# MBC1_1-3.net
KiCad netlist of a schematic drawn in EAGLE
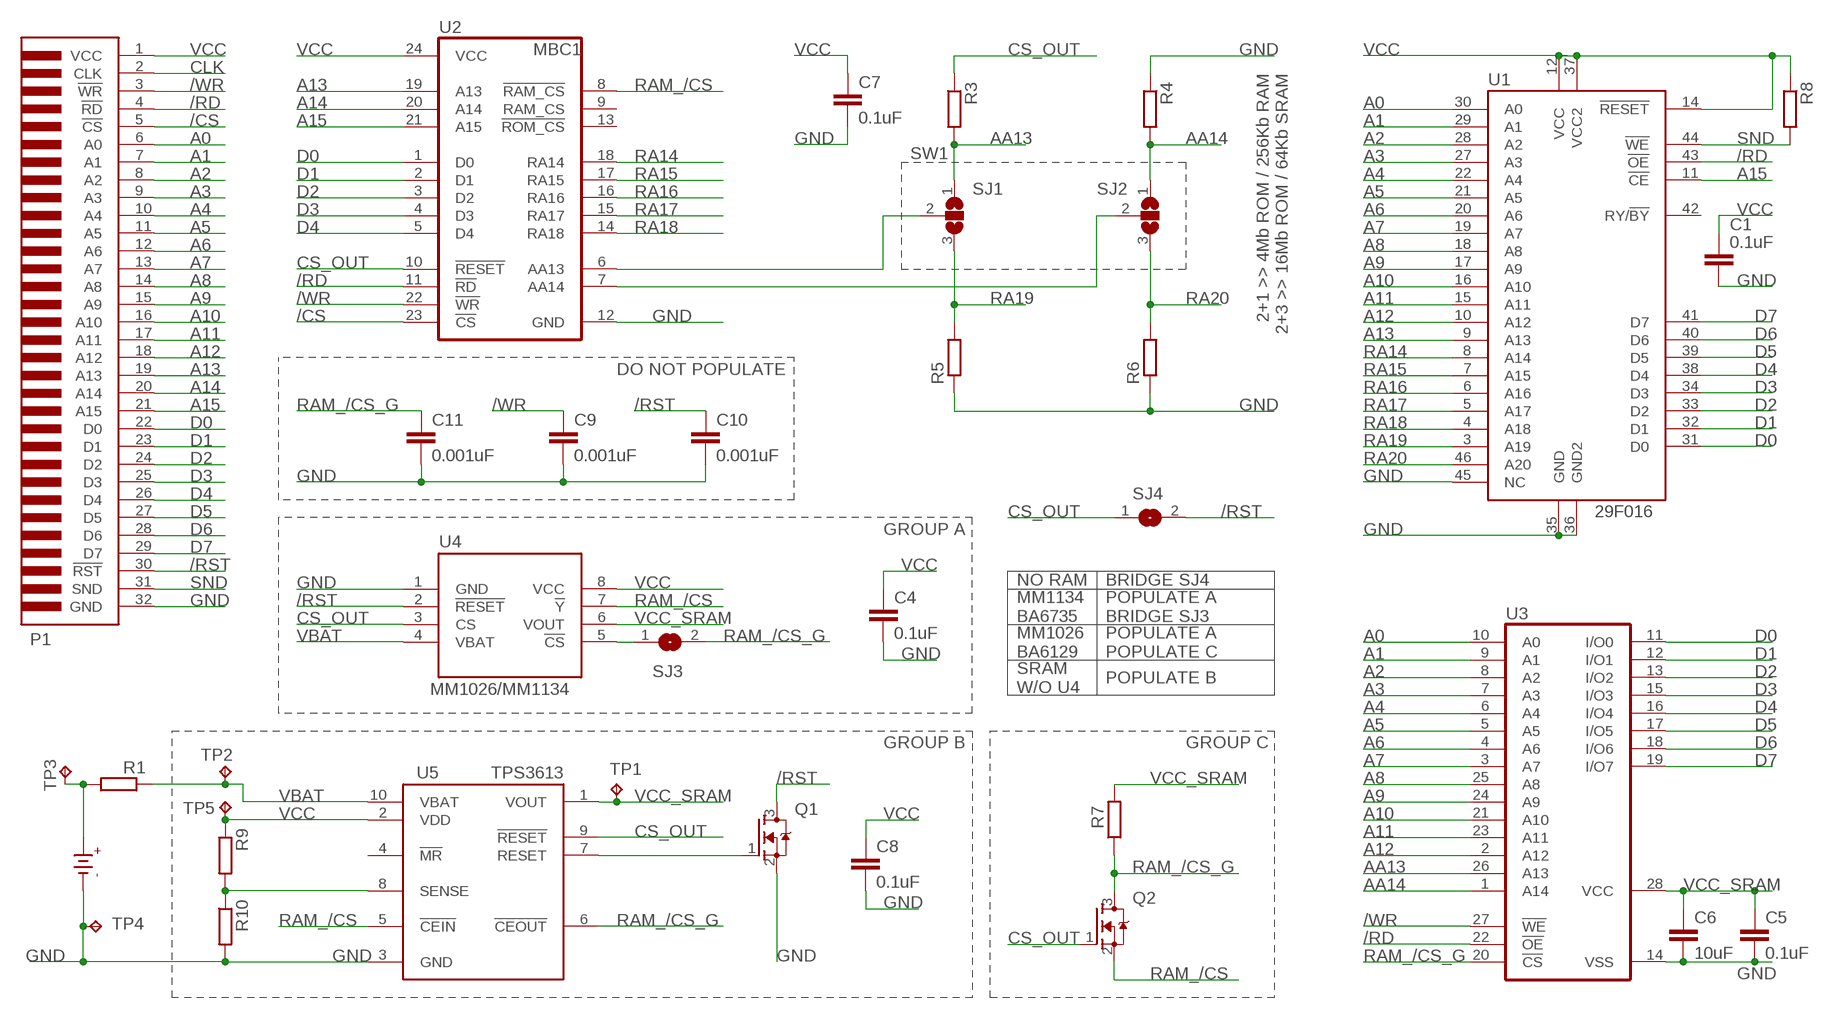
[diagram p0: schematic, sheet 1]

(export (version "E")
  (design (tool "Eeschema 10.0.6"))
  (components
    (comp (ref "B1")
      (value "CR2025")
      (footprint "eagle-import:CR2025")
      (libsource (lib "eagle-import") (part "CR2025"))
    )
    (comp (ref "C1")
      (value "0.1uF")
      (footprint "eagle-import:C0603")
      (libsource (lib "eagle-import") (part "C-EUC0603"))
    )
    (comp (ref "C4")
      (value "0.1uF")
      (footprint "eagle-import:C0603")
      (libsource (lib "eagle-import") (part "C-EUC0603"))
    )
    (comp (ref "C5")
      (value "0.1uF")
      (footprint "eagle-import:C0603")
      (libsource (lib "eagle-import") (part "C-EUC0603"))
    )
    (comp (ref "C6")
      (value "10uF")
      (footprint "eagle-import:C0603")
      (libsource (lib "eagle-import") (part "C-EUC0603"))
    )
    (comp (ref "C7")
      (value "0.1uF")
      (footprint "eagle-import:C0603")
      (libsource (lib "eagle-import") (part "C-EUC0603"))
    )
    (comp (ref "C8")
      (value "0.1uF")
      (footprint "eagle-import:C0603")
      (libsource (lib "eagle-import") (part "C-EUC0603"))
    )
    (comp (ref "C9")
      (value "0.001uF")
      (footprint "eagle-import:C0603")
      (libsource (lib "eagle-import") (part "C-EUC0603"))
    )
    (comp (ref "C10")
      (value "0.001uF")
      (footprint "eagle-import:C0603")
      (libsource (lib "eagle-import") (part "C-EUC0603"))
    )
    (comp (ref "C11")
      (value "0.001uF")
      (footprint "eagle-import:C0603")
      (libsource (lib "eagle-import") (part "C-EUC0603"))
    )
    (comp (ref "P1")
      (value "GBC_CART")
      (footprint "eagle-import:GBC_CART")
      (libsource (lib "eagle-import") (part "GBC_CART"))
    )
    (comp (ref "Q1")
      (value "2N7002")
      (footprint "eagle-import:SOT23")
      (libsource (lib "eagle-import") (part "MOSFET-NREFLOW"))
    )
    (comp (ref "Q2")
      (value "2N7002")
      (footprint "eagle-import:SOT23")
      (libsource (lib "eagle-import") (part "MOSFET-NREFLOW"))
    )
    (comp (ref "R1")
      (value "RR0603")
      (footprint "eagle-import:R0603")
      (libsource (lib "eagle-import") (part "RR0603"))
    )
    (comp (ref "R3")
      (value "RR0603")
      (footprint "eagle-import:R0603")
      (libsource (lib "eagle-import") (part "RR0603"))
    )
    (comp (ref "R4")
      (value "RR0603")
      (footprint "eagle-import:R0603")
      (libsource (lib "eagle-import") (part "RR0603"))
    )
    (comp (ref "R5")
      (value "RR0603")
      (footprint "eagle-import:R0603")
      (libsource (lib "eagle-import") (part "RR0603"))
    )
    (comp (ref "R6")
      (value "RR0603")
      (footprint "eagle-import:R0603")
      (libsource (lib "eagle-import") (part "RR0603"))
    )
    (comp (ref "R7")
      (value "RR0603")
      (footprint "eagle-import:R0603")
      (libsource (lib "eagle-import") (part "RR0603"))
    )
    (comp (ref "R8")
      (value "RR0603")
      (footprint "eagle-import:R0603")
      (libsource (lib "eagle-import") (part "RR0603"))
    )
    (comp (ref "R9")
      (value "RR0603")
      (footprint "eagle-import:R0603")
      (libsource (lib "eagle-import") (part "RR0603"))
    )
    (comp (ref "R10")
      (value "RR0603")
      (footprint "eagle-import:R0603")
      (libsource (lib "eagle-import") (part "RR0603"))
    )
    (comp (ref "SJ1")
      (value "SJ2W")
      (footprint "eagle-import:SJ_2")
      (libsource (lib "eagle-import") (part "SJ2W"))
    )
    (comp (ref "SJ2")
      (value "SJ2W")
      (footprint "eagle-import:SJ_2")
      (libsource (lib "eagle-import") (part "SJ2W"))
    )
    (comp (ref "SJ3") (value "SJ") (footprint "eagle-import:SJ") (libsource (lib "eagle-import") (part "SJ")))
    (comp (ref "SJ4") (value "SJ") (footprint "eagle-import:SJ") (libsource (lib "eagle-import") (part "SJ")))
    (comp (ref "TP1")
      (value "TPB1,27")
      (footprint "eagle-import:B1,27")
      (libsource (lib "eagle-import") (part "TPB1,27"))
    )
    (comp (ref "TP2")
      (value "TPB1,27")
      (footprint "eagle-import:B1,27")
      (libsource (lib "eagle-import") (part "TPB1,27"))
    )
    (comp (ref "TP3")
      (value "TPB1,27")
      (footprint "eagle-import:B1,27")
      (libsource (lib "eagle-import") (part "TPB1,27"))
    )
    (comp (ref "TP4")
      (value "TPB1,27")
      (footprint "eagle-import:B1,27")
      (libsource (lib "eagle-import") (part "TPB1,27"))
    )
    (comp (ref "TP5")
      (value "TPB1,27")
      (footprint "eagle-import:B1,27")
      (libsource (lib "eagle-import") (part "TPB1,27"))
    )
    (comp (ref "U1")
      (value "29F016")
      (footprint "eagle-import:TSOP-48")
      (libsource (lib "eagle-import") (part "29F016"))
    )
    (comp (ref "U2")
      (value "MBC1")
      (footprint "eagle-import:SOP-24")
      (libsource (lib "eagle-import") (part "MBC1"))
    )
    (comp (ref "U3")
      (value "62256_SRAM")
      (footprint "eagle-import:SOP-28L")
      (fields (field (name "MPN") "CY62256VNLL-70SNXI"))
      (libsource (lib "eagle-import") (part "62256_SRAM"))
    )
    (comp (ref "U4")
      (value "MM1134")
      (footprint "eagle-import:SOIC-8")
      (libsource (lib "eagle-import") (part "MM1134"))
    )
    (comp (ref "U5")
      (value "TPS3613")
      (footprint "eagle-import:MSOP-10")
      (libsource (lib "eagle-import") (part "TPS3613"))
    )
  )
  (nets
    (net (code "1") (name "/A0") (class "Default")
      (node (ref "P1") (pin "6") (pinfunction "A0_6") (pintype "output"))
      (node (ref "U1") (pin "30") (pinfunction "A0_30") (pintype "input"))
      (node (ref "U3") (pin "10") (pinfunction "A0_10") (pintype "input"))
    )
    (net (code "2") (name "/A1") (class "Default")
      (node (ref "P1") (pin "7") (pinfunction "A1_7") (pintype "output"))
      (node (ref "U1") (pin "29") (pinfunction "A1_29") (pintype "input"))
      (node (ref "U3") (pin "9") (pinfunction "A1_9") (pintype "input"))
    )
    (net (code "3") (name "/A2") (class "Default")
      (node (ref "P1") (pin "8") (pinfunction "A2_8") (pintype "output"))
      (node (ref "U1") (pin "28") (pinfunction "A2_28") (pintype "input"))
      (node (ref "U3") (pin "8") (pinfunction "A2_8") (pintype "input"))
    )
    (net (code "4") (name "/A3") (class "Default")
      (node (ref "P1") (pin "9") (pinfunction "A3_9") (pintype "output"))
      (node (ref "U1") (pin "27") (pinfunction "A3_27") (pintype "input"))
      (node (ref "U3") (pin "7") (pinfunction "A3_7") (pintype "input"))
    )
    (net (code "5") (name "/A4") (class "Default")
      (node (ref "P1") (pin "10") (pinfunction "A4_10") (pintype "output"))
      (node (ref "U1") (pin "22") (pinfunction "A4_22") (pintype "input"))
      (node (ref "U3") (pin "6") (pinfunction "A4_6") (pintype "input"))
    )
    (net (code "6") (name "/A5") (class "Default")
      (node (ref "P1") (pin "11") (pinfunction "A5_11") (pintype "output"))
      (node (ref "U1") (pin "21") (pinfunction "A5_21") (pintype "input"))
      (node (ref "U3") (pin "5") (pinfunction "A5_5") (pintype "input"))
    )
    (net (code "7") (name "/A6") (class "Default")
      (node (ref "P1") (pin "12") (pinfunction "A6_12") (pintype "output"))
      (node (ref "U1") (pin "20") (pinfunction "A6_20") (pintype "input"))
      (node (ref "U3") (pin "4") (pinfunction "A6_4") (pintype "input"))
    )
    (net (code "8") (name "/A7") (class "Default")
      (node (ref "P1") (pin "13") (pinfunction "A7_13") (pintype "output"))
      (node (ref "U1") (pin "19") (pinfunction "A7_19") (pintype "input"))
      (node (ref "U3") (pin "3") (pinfunction "A7_3") (pintype "input"))
    )
    (net (code "9") (name "/A8") (class "Default")
      (node (ref "P1") (pin "14") (pinfunction "A8_14") (pintype "output"))
      (node (ref "U1") (pin "18") (pinfunction "A8_18") (pintype "input"))
      (node (ref "U3") (pin "25") (pinfunction "A8_25") (pintype "input"))
    )
    (net (code "10") (name "/A9") (class "Default")
      (node (ref "P1") (pin "15") (pinfunction "A9_15") (pintype "output"))
      (node (ref "U1") (pin "17") (pinfunction "A9_17") (pintype "input"))
      (node (ref "U3") (pin "24") (pinfunction "A9_24") (pintype "input"))
    )
    (net (code "11") (name "/A10") (class "Default")
      (node (ref "P1") (pin "16") (pinfunction "A10_16") (pintype "output"))
      (node (ref "U1") (pin "16") (pinfunction "A10_16") (pintype "input"))
      (node (ref "U3") (pin "21") (pinfunction "A10_21") (pintype "input"))
    )
    (net (code "12") (name "/A11") (class "Default")
      (node (ref "P1") (pin "17") (pinfunction "A11_17") (pintype "output"))
      (node (ref "U1") (pin "15") (pinfunction "A11_15") (pintype "input"))
      (node (ref "U3") (pin "23") (pinfunction "A11_23") (pintype "input"))
    )
    (net (code "13") (name "/A12") (class "Default")
      (node (ref "P1") (pin "18") (pinfunction "A12_18") (pintype "output"))
      (node (ref "U1") (pin "10") (pinfunction "A12_10") (pintype "input"))
      (node (ref "U3") (pin "2") (pinfunction "A12_2") (pintype "input"))
    )
    (net (code "14") (name "/A13") (class "Default")
      (node (ref "P1") (pin "19") (pinfunction "A13_19") (pintype "output"))
      (node (ref "U1") (pin "9") (pinfunction "A13_9") (pintype "input"))
      (node (ref "U2") (pin "19") (pinfunction "A13_19") (pintype "input"))
    )
    (net (code "15") (name "/A14") (class "Default")
      (node (ref "P1") (pin "20") (pinfunction "A14_20") (pintype "output"))
      (node (ref "U2") (pin "20") (pinfunction "A14_20") (pintype "input"))
    )
    (net (code "16") (name "/A15") (class "Default")
      (node (ref "P1") (pin "21") (pinfunction "A15_21") (pintype "output"))
      (node (ref "U1") (pin "11") (pinfunction "~{CE}_11") (pintype "input"))
      (node (ref "U2") (pin "21") (pinfunction "A15_21") (pintype "input"))
    )
    (net (code "17") (name "/AA13") (class "Default")
      (node (ref "R3") (pin "2") (pinfunction "2_2") (pintype "passive"))
      (node (ref "SJ1") (pin "1") (pinfunction "1_1") (pintype "passive"))
      (node (ref "U3") (pin "26") (pinfunction "A13_26") (pintype "input"))
    )
    (net (code "18") (name "/AA14") (class "Default")
      (node (ref "R4") (pin "2") (pinfunction "2_2") (pintype "passive"))
      (node (ref "SJ2") (pin "1") (pinfunction "1_1") (pintype "passive"))
      (node (ref "U3") (pin "1") (pinfunction "A14_1") (pintype "input"))
    )
    (net (code "19") (name "/CLK") (class "Default")
      (node (ref "P1") (pin "2") (pinfunction "CLK_2") (pintype "output"))
    )
    (net (code "20") (name "/CS_OUT") (class "Default")
      (node (ref "Q2") (pin "1") (pinfunction "G_1") (pintype "bidirectional"))
      (node (ref "R3") (pin "1") (pinfunction "1_1") (pintype "passive"))
      (node (ref "SJ4") (pin "1") (pinfunction "1_1") (pintype "passive"))
      (node (ref "U2") (pin "10") (pinfunction "~{RESET}_10") (pintype "input"))
      (node (ref "U4") (pin "3") (pinfunction "CS_3") (pintype "output"))
      (node (ref "U5") (pin "9") (pinfunction "~{RESET}_9") (pintype "output"))
    )
    (net (code "21") (name "/D0") (class "Default")
      (node (ref "P1") (pin "22") (pinfunction "D0_22") (pintype "bidirectional"))
      (node (ref "U1") (pin "31") (pinfunction "D0_31") (pintype "bidirectional"))
      (node (ref "U2") (pin "1") (pinfunction "D0_1") (pintype "input"))
      (node (ref "U3") (pin "11") (pinfunction "I/O0_11") (pintype "bidirectional"))
    )
    (net (code "22") (name "/D1") (class "Default")
      (node (ref "P1") (pin "23") (pinfunction "D1_23") (pintype "bidirectional"))
      (node (ref "U1") (pin "32") (pinfunction "D1_32") (pintype "bidirectional"))
      (node (ref "U2") (pin "2") (pinfunction "D1_2") (pintype "input"))
      (node (ref "U3") (pin "12") (pinfunction "I/O1_12") (pintype "bidirectional"))
    )
    (net (code "23") (name "/D2") (class "Default")
      (node (ref "P1") (pin "24") (pinfunction "D2_24") (pintype "bidirectional"))
      (node (ref "U1") (pin "33") (pinfunction "D2_33") (pintype "bidirectional"))
      (node (ref "U2") (pin "3") (pinfunction "D2_3") (pintype "input"))
      (node (ref "U3") (pin "13") (pinfunction "I/O2_13") (pintype "bidirectional"))
    )
    (net (code "24") (name "/D3") (class "Default")
      (node (ref "P1") (pin "25") (pinfunction "D3_25") (pintype "bidirectional"))
      (node (ref "U1") (pin "34") (pinfunction "D3_34") (pintype "bidirectional"))
      (node (ref "U2") (pin "4") (pinfunction "D3_4") (pintype "input"))
      (node (ref "U3") (pin "15") (pinfunction "I/O3_15") (pintype "bidirectional"))
    )
    (net (code "25") (name "/D4") (class "Default")
      (node (ref "P1") (pin "26") (pinfunction "D4_26") (pintype "bidirectional"))
      (node (ref "U1") (pin "38") (pinfunction "D4_38") (pintype "bidirectional"))
      (node (ref "U2") (pin "5") (pinfunction "D4_5") (pintype "input"))
      (node (ref "U3") (pin "16") (pinfunction "I/O4_16") (pintype "bidirectional"))
    )
    (net (code "26") (name "/D5") (class "Default")
      (node (ref "P1") (pin "27") (pinfunction "D5_27") (pintype "bidirectional"))
      (node (ref "U1") (pin "39") (pinfunction "D5_39") (pintype "bidirectional"))
      (node (ref "U3") (pin "17") (pinfunction "I/O5_17") (pintype "bidirectional"))
    )
    (net (code "27") (name "/D6") (class "Default")
      (node (ref "P1") (pin "28") (pinfunction "D6_28") (pintype "bidirectional"))
      (node (ref "U1") (pin "40") (pinfunction "D6_40") (pintype "bidirectional"))
      (node (ref "U3") (pin "18") (pinfunction "I/O6_18") (pintype "bidirectional"))
    )
    (net (code "28") (name "/D7") (class "Default")
      (node (ref "P1") (pin "29") (pinfunction "D7_29") (pintype "bidirectional"))
      (node (ref "U1") (pin "41") (pinfunction "D7_41") (pintype "bidirectional"))
      (node (ref "U3") (pin "19") (pinfunction "I/O7_19") (pintype "bidirectional"))
    )
    (net (code "29") (name "/GND") (class "Default")
      (node (ref "B1") (pin "-") (pinfunction "-_-") (pintype "power_in"))
      (node (ref "C1") (pin "2") (pinfunction "2_2") (pintype "passive"))
      (node (ref "C10") (pin "2") (pinfunction "2_2") (pintype "passive"))
      (node (ref "C11") (pin "2") (pinfunction "2_2") (pintype "passive"))
      (node (ref "C4") (pin "2") (pinfunction "2_2") (pintype "passive"))
      (node (ref "C5") (pin "2") (pinfunction "2_2") (pintype "passive"))
      (node (ref "C6") (pin "2") (pinfunction "2_2") (pintype "passive"))
      (node (ref "C7") (pin "2") (pinfunction "2_2") (pintype "passive"))
      (node (ref "C8") (pin "2") (pinfunction "2_2") (pintype "passive"))
      (node (ref "C9") (pin "2") (pinfunction "2_2") (pintype "passive"))
      (node (ref "P1") (pin "32") (pinfunction "GND_32") (pintype "power_in"))
      (node (ref "Q1") (pin "2") (pinfunction "S_2") (pintype "bidirectional"))
      (node (ref "R10") (pin "2") (pinfunction "2_2") (pintype "passive"))
      (node (ref "R4") (pin "1") (pinfunction "1_1") (pintype "passive"))
      (node (ref "R5") (pin "1") (pinfunction "1_1") (pintype "passive"))
      (node (ref "R6") (pin "1") (pinfunction "1_1") (pintype "passive"))
      (node (ref "TP4") (pin "TP") (pinfunction "TP_TP") (pintype "input"))
      (node (ref "U1") (pin "35") (pinfunction "GND_35") (pintype "power_in"))
      (node (ref "U1") (pin "36") (pinfunction "GND2_36") (pintype "power_in"))
      (node (ref "U1") (pin "45") (pinfunction "NC_45") (pintype "input"))
      (node (ref "U2") (pin "12") (pinfunction "GND_12") (pintype "power_in"))
      (node (ref "U3") (pin "14") (pinfunction "VSS_14") (pintype "power_in"))
      (node (ref "U4") (pin "1") (pinfunction "GND_1") (pintype "power_in"))
      (node (ref "U5") (pin "3") (pinfunction "GND_3") (pintype "power_in"))
    )
    (net (code "30") (name "/RA14") (class "Default")
      (node (ref "U1") (pin "8") (pinfunction "A14_8") (pintype "input"))
      (node (ref "U2") (pin "18") (pinfunction "RA14_18") (pintype "output"))
    )
    (net (code "31") (name "/RA15") (class "Default")
      (node (ref "U1") (pin "7") (pinfunction "A15_7") (pintype "input"))
      (node (ref "U2") (pin "17") (pinfunction "RA15_17") (pintype "output"))
    )
    (net (code "32") (name "/RA16") (class "Default")
      (node (ref "U1") (pin "6") (pinfunction "A16_6") (pintype "input"))
      (node (ref "U2") (pin "16") (pinfunction "RA16_16") (pintype "output"))
    )
    (net (code "33") (name "/RA17") (class "Default")
      (node (ref "U1") (pin "5") (pinfunction "A17_5") (pintype "input"))
      (node (ref "U2") (pin "15") (pinfunction "RA17_15") (pintype "output"))
    )
    (net (code "34") (name "/RA18") (class "Default")
      (node (ref "U1") (pin "4") (pinfunction "A18_4") (pintype "input"))
      (node (ref "U2") (pin "14") (pinfunction "RA18_14") (pintype "output"))
    )
    (net (code "35") (name "/RA19") (class "Default")
      (node (ref "R5") (pin "2") (pinfunction "2_2") (pintype "passive"))
      (node (ref "SJ1") (pin "3") (pinfunction "3_3") (pintype "passive"))
      (node (ref "U1") (pin "3") (pinfunction "A19_3") (pintype "input"))
    )
    (net (code "36") (name "/RA20") (class "Default")
      (node (ref "R6") (pin "2") (pinfunction "2_2") (pintype "passive"))
      (node (ref "SJ2") (pin "3") (pinfunction "3_3") (pintype "passive"))
      (node (ref "U1") (pin "46") (pinfunction "A20_46") (pintype "input"))
    )
    (net (code "37") (name "/RAM_{slash}CS") (class "Default")
      (node (ref "Q2") (pin "2") (pinfunction "S_2") (pintype "bidirectional"))
      (node (ref "U2") (pin "8") (pinfunction "~{RAM_CS}_8") (pintype "output"))
      (node (ref "U4") (pin "7") (pinfunction "~{Y}_7") (pintype "input"))
      (node (ref "U5") (pin "5") (pinfunction "~{CEIN}_5") (pintype "input"))
    )
    (net (code "38") (name "/RAM_{slash}CS_G") (class "Default")
      (node (ref "C11") (pin "1") (pinfunction "1_1") (pintype "passive"))
      (node (ref "Q2") (pin "3") (pinfunction "D_3") (pintype "bidirectional"))
      (node (ref "R7") (pin "1") (pinfunction "1_1") (pintype "passive"))
      (node (ref "SJ3") (pin "2") (pinfunction "2_2") (pintype "passive"))
      (node (ref "U3") (pin "20") (pinfunction "~{CS}_20") (pintype "input"))
      (node (ref "U5") (pin "6") (pinfunction "~{CEOUT}_6") (pintype "output"))
    )
    (net (code "39") (name "/SND") (class "Default")
      (node (ref "P1") (pin "31") (pinfunction "SND_31") (pintype "bidirectional"))
      (node (ref "R8") (pin "2") (pinfunction "2_2") (pintype "passive"))
      (node (ref "U1") (pin "44") (pinfunction "~{WE}_44") (pintype "input"))
    )
    (net (code "40") (name "/VBAT") (class "Default")
      (node (ref "R1") (pin "1") (pinfunction "1_1") (pintype "passive"))
      (node (ref "TP2") (pin "TP") (pinfunction "TP_TP") (pintype "input"))
      (node (ref "U4") (pin "4") (pinfunction "VBAT_4") (pintype "power_in"))
      (node (ref "U5") (pin "10") (pinfunction "VBAT_10") (pintype "power_in"))
    )
    (net (code "41") (name "/VCC") (class "Default")
      (node (ref "C1") (pin "1") (pinfunction "1_1") (pintype "passive"))
      (node (ref "C4") (pin "1") (pinfunction "1_1") (pintype "passive"))
      (node (ref "C7") (pin "1") (pinfunction "1_1") (pintype "passive"))
      (node (ref "C8") (pin "1") (pinfunction "1_1") (pintype "passive"))
      (node (ref "P1") (pin "1") (pinfunction "VCC_1") (pintype "power_in"))
      (node (ref "R8") (pin "1") (pinfunction "1_1") (pintype "passive"))
      (node (ref "R9") (pin "1") (pinfunction "1_1") (pintype "passive"))
      (node (ref "TP5") (pin "TP") (pinfunction "TP_TP") (pintype "input"))
      (node (ref "U1") (pin "12") (pinfunction "VCC_12") (pintype "power_in"))
      (node (ref "U1") (pin "14") (pinfunction "~{RESET}_14") (pintype "input"))
      (node (ref "U1") (pin "37") (pinfunction "VCC2_37") (pintype "power_in"))
      (node (ref "U2") (pin "24") (pinfunction "VCC_24") (pintype "power_in"))
      (node (ref "U4") (pin "8") (pinfunction "VCC_8") (pintype "power_in"))
      (node (ref "U5") (pin "2") (pinfunction "VDD_2") (pintype "power_in"))
    )
    (net (code "42") (name "/VCC_SRAM") (class "Default")
      (node (ref "C5") (pin "1") (pinfunction "1_1") (pintype "passive"))
      (node (ref "C6") (pin "1") (pinfunction "1_1") (pintype "passive"))
      (node (ref "R7") (pin "2") (pinfunction "2_2") (pintype "passive"))
      (node (ref "TP1") (pin "TP") (pinfunction "TP_TP") (pintype "input"))
      (node (ref "U3") (pin "28") (pinfunction "VCC_28") (pintype "power_in"))
      (node (ref "U4") (pin "6") (pinfunction "VOUT_6") (pintype "power_in"))
      (node (ref "U5") (pin "1") (pinfunction "VOUT_1") (pintype "power_in"))
    )
    (net (code "43") (name "/{slash}CS") (class "Default")
      (node (ref "P1") (pin "5") (pinfunction "~{CS}_5") (pintype "output"))
      (node (ref "U2") (pin "23") (pinfunction "~{CS}_23") (pintype "input"))
    )
    (net (code "44") (name "/{slash}RD") (class "Default")
      (node (ref "P1") (pin "4") (pinfunction "~{RD}_4") (pintype "output"))
      (node (ref "U1") (pin "43") (pinfunction "~{OE}_43") (pintype "input"))
      (node (ref "U2") (pin "11") (pinfunction "~{RD}_11") (pintype "input"))
      (node (ref "U3") (pin "22") (pinfunction "~{OE}_22") (pintype "input"))
    )
    (net (code "45") (name "/{slash}RST") (class "Default")
      (node (ref "C10") (pin "1") (pinfunction "1_1") (pintype "passive"))
      (node (ref "P1") (pin "30") (pinfunction "~{RST}_30") (pintype "bidirectional"))
      (node (ref "Q1") (pin "3") (pinfunction "D_3") (pintype "bidirectional"))
      (node (ref "SJ4") (pin "2") (pinfunction "2_2") (pintype "passive"))
      (node (ref "U4") (pin "2") (pinfunction "~{RESET}_2") (pintype "input"))
    )
    (net (code "46") (name "/{slash}WR") (class "Default")
      (node (ref "C9") (pin "1") (pinfunction "1_1") (pintype "passive"))
      (node (ref "P1") (pin "3") (pinfunction "~{WR}_3") (pintype "output"))
      (node (ref "U2") (pin "22") (pinfunction "~{WR}_22") (pintype "input"))
      (node (ref "U3") (pin "27") (pinfunction "~{WE}_27") (pintype "input"))
    )
    (net (code "47") (name "Net-(B1-Pad+)") (class "Default")
      (node (ref "B1") (pin "+") (pinfunction "+_+") (pintype "power_in"))
      (node (ref "R1") (pin "2") (pinfunction "2_2") (pintype "passive"))
      (node (ref "TP3") (pin "TP") (pinfunction "TP_TP") (pintype "input"))
    )
    (net (code "48") (name "Net-(Q1-G)") (class "Default")
      (node (ref "Q1") (pin "1") (pinfunction "G_1") (pintype "bidirectional"))
      (node (ref "U5") (pin "7") (pinfunction "RESET_7") (pintype "output"))
    )
    (net (code "49") (name "Net-(U2-AA13)") (class "Default")
      (node (ref "SJ1") (pin "2") (pinfunction "2_2") (pintype "passive"))
      (node (ref "U2") (pin "6") (pinfunction "AA13_6") (pintype "output"))
    )
    (net (code "50") (name "Net-(U2-AA14)") (class "Default")
      (node (ref "SJ2") (pin "2") (pinfunction "2_2") (pintype "passive"))
      (node (ref "U2") (pin "7") (pinfunction "AA14_7") (pintype "output"))
    )
    (net (code "51") (name "Net-(U4-~{CS})") (class "Default")
      (node (ref "SJ3") (pin "1") (pinfunction "1_1") (pintype "passive"))
      (node (ref "U4") (pin "5") (pinfunction "~{CS}_5") (pintype "output"))
    )
    (net (code "52") (name "Net-(U5-SENSE)") (class "Default")
      (node (ref "R10") (pin "1") (pinfunction "1_1") (pintype "passive"))
      (node (ref "R9") (pin "2") (pinfunction "2_2") (pintype "passive"))
      (node (ref "U5") (pin "8") (pinfunction "SENSE_8") (pintype "input"))
    )
    (net (code "53") (name "unconnected-(U1-RY{slash}~{BY}-Pad42)") (class "Default")
      (node (ref "U1") (pin "42") (pinfunction "RY/~{BY}_42") (pintype "output"))
    )
    (net (code "54") (name "unconnected-(U2-RAM_CS-Pad9)") (class "Default")
      (node (ref "U2") (pin "9") (pinfunction "RAM_CS_9") (pintype "output"))
    )
    (net (code "55") (name "unconnected-(U2-~{ROM_CS}-Pad13)") (class "Default")
      (node (ref "U2") (pin "13") (pinfunction "~{ROM_CS}_13") (pintype "output"))
    )
    (net (code "56") (name "unconnected-(U5-~{MR}-Pad4)") (class "Default")
      (node (ref "U5") (pin "4") (pinfunction "~{MR}_4") (pintype "input"))
    )
  )
)
